# NBModule.net
KiCad netlist of a schematic drawn in Altium Designer
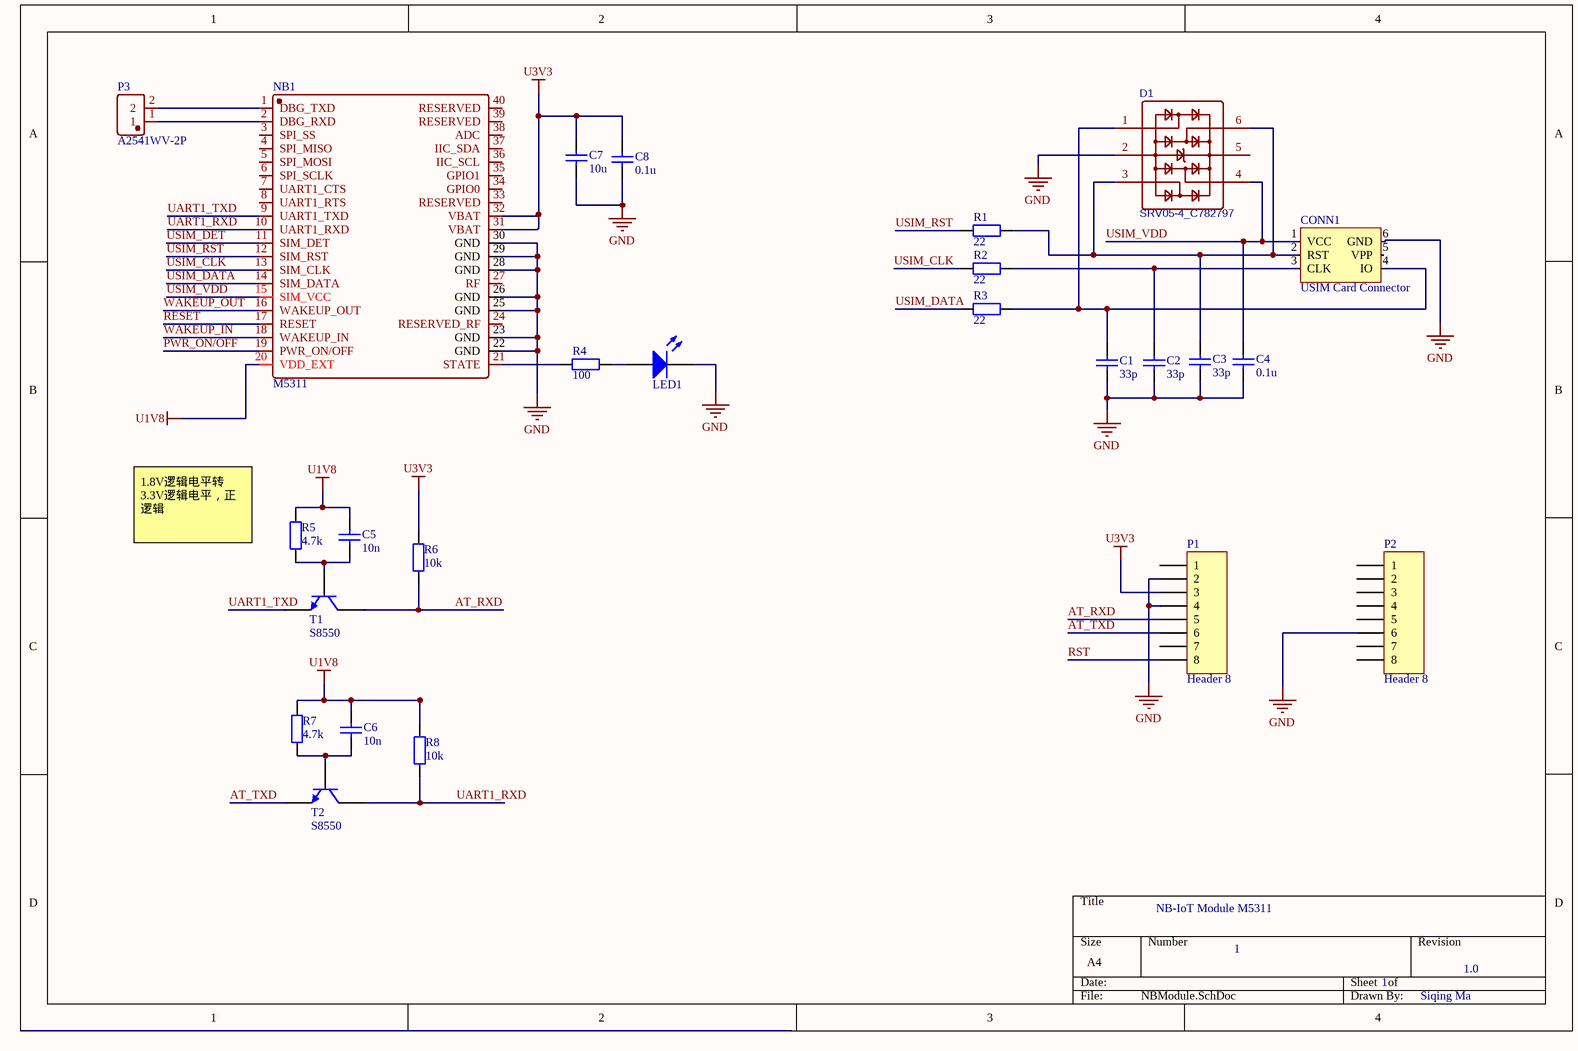
[diagram p0: NBModule.SchDoc]

(export (version "E")
  (design (tool "Eeschema 10.0.6"))
  (components
    (comp (ref "C1")
      (value "33p")
      (footprint "C 1206")
      (description "1206贴片电容")
      (libsource (lib "02-Miscellaneous_Devices_ZSF_Library") (part "Cap_1206"))
    )
    (comp (ref "C2")
      (value "33p")
      (footprint "C 1206")
      (description "1206贴片电容")
      (libsource (lib "02-Miscellaneous_Devices_ZSF_Library") (part "Cap_1206"))
    )
    (comp (ref "C3")
      (value "33p")
      (footprint "C 1206")
      (description "1206贴片电容")
      (libsource (lib "02-Miscellaneous_Devices_ZSF_Library") (part "Cap_1206"))
    )
    (comp (ref "C4")
      (value "0.1u")
      (footprint "C 1206")
      (description "1206贴片电容")
      (libsource (lib "02-Miscellaneous_Devices_ZSF_Library") (part "Cap_1206"))
    )
    (comp (ref "C5")
      (value "10n")
      (footprint "C 1206")
      (description "1206贴片电容")
      (libsource (lib "02-Miscellaneous_Devices_ZSF_Library") (part "Cap_1206"))
    )
    (comp (ref "C6")
      (value "10n")
      (footprint "C 1206")
      (description "1206贴片电容")
      (libsource (lib "02-Miscellaneous_Devices_ZSF_Library") (part "Cap_1206"))
    )
    (comp (ref "C7")
      (value "10u")
      (footprint "C 1206")
      (description "1206贴片电容")
      (libsource (lib "02-Miscellaneous_Devices_ZSF_Library") (part "Cap_1206"))
    )
    (comp (ref "C8")
      (value "0.1u")
      (footprint "C 1206")
      (description "1206贴片电容")
      (libsource (lib "02-Miscellaneous_Devices_ZSF_Library") (part "Cap_1206"))
    )
    (comp (ref "CONN1")
      (value "USIM Card Connector")
      (footprint "SIM-SMD_SMO-1512")
      (libsource (lib "NBIoT") (part "USIM Card Connector"))
    )
    (comp (ref "D1")
      (value "SRV05-4_C782797")
      (footprint "SOT-23-6_L2.9-W1.6-P0.95-LS2.8-BR")
      (fields
        (field (name "BOM_SUPPLIER PART") "C782797")
        (field (name "BOM_MANUFACTURER PART") "SRV05-4")
        (field (name "CONTRIBUTOR") "LCSC")
      )
      (libsource (lib "NBIoT") (part "SRV05-4_C782797"))
    )
    (comp (ref "LED1")
      (value "LED Chip")
      (footprint "LED 1206R")
      (description "Typical Chip LED")
      (fields (field (name "PUBLISHER") "Altium Limited"))
      (libsource (lib "03-EButterflyIntegratedLibrary") (part "LED Chip"))
    )
    (comp (ref "NB1") (value "M5311") (footprint "M5311") (libsource (lib "NBIoT") (part "M5311")))
    (comp (ref "P1")
      (value "Header 8")
      (footprint "HDR1X8")
      (description "Header, 8-Pin")
      (fields (field (name "PUBLISHER") "Altium Limited"))
      (libsource (lib "Miscellaneous Connectors") (part "Header 8"))
    )
    (comp (ref "P2")
      (value "Header 8")
      (footprint "HDR1X8")
      (description "Header, 8-Pin")
      (fields (field (name "PUBLISHER") "Altium Limited"))
      (libsource (lib "Miscellaneous Connectors") (part "Header 8"))
    )
    (comp (ref "P3")
      (value "A2541WV-2P")
      (footprint "HDR-TH_P2.54-H-M_A2541WV-2P")
      (libsource (lib "NBIoT") (part "A2541WV-2P"))
    )
    (comp (ref "R1")
      (value "22")
      (footprint "R 0805")
      (description "0805贴片电阻")
      (libsource (lib "02-Miscellaneous_Devices_ZSF_Library") (part "Res_0805"))
    )
    (comp (ref "R2")
      (value "22")
      (footprint "R 0805")
      (description "0805贴片电阻")
      (libsource (lib "02-Miscellaneous_Devices_ZSF_Library") (part "Res_0805"))
    )
    (comp (ref "R3")
      (value "22")
      (footprint "R 0805")
      (description "0805贴片电阻")
      (libsource (lib "02-Miscellaneous_Devices_ZSF_Library") (part "Res_0805"))
    )
    (comp (ref "R4")
      (value "100")
      (footprint "R 0805")
      (description "0805贴片电阻")
      (libsource (lib "02-Miscellaneous_Devices_ZSF_Library") (part "Res_0805"))
    )
    (comp (ref "R5")
      (value "4.7k")
      (footprint "R 0805")
      (description "0805贴片电阻")
      (libsource (lib "") (part "Res_0805_1"))
    )
    (comp (ref "R6")
      (value "10k")
      (footprint "R 0805")
      (description "0805贴片电阻")
      (libsource (lib "") (part "Res_0805_1"))
    )
    (comp (ref "R7")
      (value "4.7k")
      (footprint "R 0805")
      (description "0805贴片电阻")
      (libsource (lib "") (part "Res_0805_1"))
    )
    (comp (ref "R8")
      (value "10k")
      (footprint "R 0805")
      (description "0805贴片电阻")
      (libsource (lib "") (part "Res_0805_1"))
    )
    (comp (ref "T1")
      (value "S8550")
      (footprint "SOT-23B_N")
      (description "NPN Bipolar Transistor")
      (fields (field (name "PUBLISHER") "Altium Limited"))
      (libsource (lib "Miscellaneous Devices") (part "QNPN"))
    )
    (comp (ref "T2")
      (value "S8550")
      (footprint "SOT-23B_N")
      (description "NPN Bipolar Transistor")
      (fields (field (name "PUBLISHER") "Altium Limited"))
      (libsource (lib "Miscellaneous Devices") (part "QNPN"))
    )
  )
  (nets
    (net (code "1") (name "/AT_RXD") (class "Default")
      (node (ref "P1") (pin "5") (pinfunction "5_5") (pintype "passive"))
      (node (ref "R6") (pin "2") (pinfunction "2_2") (pintype "passive"))
      (node (ref "T1") (pin "1") (pinfunction "C_1") (pintype "passive"))
    )
    (net (code "2") (name "/AT_TXD") (class "Default")
      (node (ref "P1") (pin "6") (pinfunction "6_6") (pintype "passive"))
      (node (ref "T2") (pin "3") (pinfunction "E_3") (pintype "passive"))
    )
    (net (code "3") (name "/PWR_ON{slash}OFF") (class "Default")
      (node (ref "NB1") (pin "19") (pinfunction "PWR_ON/OFF_19") (pintype "passive"))
    )
    (net (code "4") (name "/RESET") (class "Default")
      (node (ref "NB1") (pin "17") (pinfunction "RESET_17") (pintype "passive"))
    )
    (net (code "5") (name "/RST") (class "Default")
      (node (ref "P1") (pin "8") (pinfunction "8_8") (pintype "passive"))
    )
    (net (code "6") (name "/UART1_RXD") (class "Default")
      (node (ref "NB1") (pin "10") (pinfunction "UART1_RXD_10") (pintype "passive"))
      (node (ref "R8") (pin "2") (pinfunction "2_2") (pintype "passive"))
      (node (ref "T2") (pin "1") (pinfunction "C_1") (pintype "passive"))
    )
    (net (code "7") (name "/UART1_TXD") (class "Default")
      (node (ref "NB1") (pin "9") (pinfunction "UART1_TXD_9") (pintype "passive"))
      (node (ref "T1") (pin "3") (pinfunction "E_3") (pintype "passive"))
    )
    (net (code "8") (name "/USIM_CLK") (class "Default")
      (node (ref "NB1") (pin "13") (pinfunction "SIM_CLK_13") (pintype "passive"))
      (node (ref "R2") (pin "2") (pinfunction "2_2") (pintype "passive"))
    )
    (net (code "9") (name "/USIM_DATA") (class "Default")
      (node (ref "NB1") (pin "14") (pinfunction "SIM_DATA_14") (pintype "passive"))
      (node (ref "R3") (pin "2") (pinfunction "2_2") (pintype "passive"))
    )
    (net (code "10") (name "/USIM_DET") (class "Default")
      (node (ref "NB1") (pin "11") (pinfunction "SIM_DET_11") (pintype "passive"))
    )
    (net (code "11") (name "/USIM_RST") (class "Default")
      (node (ref "NB1") (pin "12") (pinfunction "SIM_RST_12") (pintype "passive"))
      (node (ref "R1") (pin "2") (pinfunction "2_2") (pintype "passive"))
    )
    (net (code "12") (name "/USIM_VDD") (class "Default")
      (node (ref "C4") (pin "2") (pinfunction "2_2") (pintype "passive"))
      (node (ref "CONN1") (pin "1") (pinfunction "VCC_1") (pintype "bidirectional"))
      (node (ref "D1") (pin "4") (pinfunction "4_4") (pintype "passive"))
      (node (ref "NB1") (pin "15") (pinfunction "SIM_VCC_15") (pintype "passive"))
    )
    (net (code "13") (name "/WAKEUP_IN") (class "Default")
      (node (ref "NB1") (pin "18") (pinfunction "WAKEUP_IN_18") (pintype "passive"))
    )
    (net (code "14") (name "/WAKEUP_OUT") (class "Default")
      (node (ref "NB1") (pin "16") (pinfunction "WAKEUP_OUT_16") (pintype "passive"))
    )
    (net (code "15") (name "GND") (class "Default")
      (node (ref "C1") (pin "1") (pinfunction "1_1") (pintype "passive"))
      (node (ref "C2") (pin "1") (pinfunction "1_1") (pintype "passive"))
      (node (ref "C3") (pin "1") (pinfunction "1_1") (pintype "passive"))
      (node (ref "C4") (pin "1") (pinfunction "1_1") (pintype "passive"))
      (node (ref "C7") (pin "1") (pinfunction "1_1") (pintype "passive"))
      (node (ref "C8") (pin "1") (pinfunction "1_1") (pintype "passive"))
      (node (ref "CONN1") (pin "6") (pinfunction "GND_6") (pintype "bidirectional"))
      (node (ref "D1") (pin "2") (pinfunction "2_2") (pintype "passive"))
      (node (ref "LED1") (pin "2") (pinfunction "K_2") (pintype "passive"))
      (node (ref "NB1") (pin "22") (pinfunction "GND_22") (pintype "passive"))
      (node (ref "NB1") (pin "23") (pinfunction "GND_23") (pintype "passive"))
      (node (ref "NB1") (pin "25") (pinfunction "GND_25") (pintype "passive"))
      (node (ref "NB1") (pin "26") (pinfunction "GND_26") (pintype "passive"))
      (node (ref "NB1") (pin "28") (pinfunction "GND_28") (pintype "passive"))
      (node (ref "NB1") (pin "29") (pinfunction "GND_29") (pintype "passive"))
      (node (ref "NB1") (pin "30") (pinfunction "GND_30") (pintype "passive"))
      (node (ref "P1") (pin "2") (pinfunction "2_2") (pintype "passive"))
      (node (ref "P1") (pin "4") (pinfunction "4_4") (pintype "passive"))
      (node (ref "P2") (pin "6") (pinfunction "6_6") (pintype "passive"))
    )
    (net (code "16") (name "Net-(CONN1-CLK)") (class "Default")
      (node (ref "C2") (pin "2") (pinfunction "2_2") (pintype "passive"))
      (node (ref "CONN1") (pin "3") (pinfunction "CLK_3") (pintype "bidirectional"))
      (node (ref "R2") (pin "1") (pinfunction "1_1") (pintype "passive"))
    )
    (net (code "17") (name "Net-(CONN1-IO)") (class "Default")
      (node (ref "C1") (pin "2") (pinfunction "2_2") (pintype "passive"))
      (node (ref "CONN1") (pin "4") (pinfunction "IO_4") (pintype "bidirectional"))
      (node (ref "D1") (pin "1") (pinfunction "1_1") (pintype "passive"))
      (node (ref "R3") (pin "1") (pinfunction "1_1") (pintype "passive"))
    )
    (net (code "18") (name "Net-(CONN1-RST)") (class "Default")
      (node (ref "C3") (pin "2") (pinfunction "2_2") (pintype "passive"))
      (node (ref "CONN1") (pin "2") (pinfunction "RST_2") (pintype "bidirectional"))
      (node (ref "D1") (pin "3") (pinfunction "3_3") (pintype "passive"))
      (node (ref "D1") (pin "6") (pinfunction "6_6") (pintype "passive"))
      (node (ref "R1") (pin "1") (pinfunction "1_1") (pintype "passive"))
    )
    (net (code "19") (name "Net-(LED1-A)") (class "Default")
      (node (ref "LED1") (pin "1") (pinfunction "A_1") (pintype "passive"))
      (node (ref "R4") (pin "1") (pinfunction "1_1") (pintype "passive"))
    )
    (net (code "20") (name "Net-(NB1-DBG_RXD)") (class "Default")
      (node (ref "NB1") (pin "2") (pinfunction "DBG_RXD_2") (pintype "passive"))
      (node (ref "P3") (pin "1") (pinfunction "1_1") (pintype "passive"))
    )
    (net (code "21") (name "Net-(NB1-DBG_TXD)") (class "Default")
      (node (ref "NB1") (pin "1") (pinfunction "DBG_TXD_1") (pintype "passive"))
      (node (ref "P3") (pin "2") (pinfunction "2_2") (pintype "passive"))
    )
    (net (code "22") (name "Net-(NB1-STATE)") (class "Default")
      (node (ref "NB1") (pin "21") (pinfunction "STATE_21") (pintype "passive"))
      (node (ref "R4") (pin "2") (pinfunction "2_2") (pintype "passive"))
    )
    (net (code "23") (name "Net-(T1-B)") (class "Default")
      (node (ref "C5") (pin "2") (pinfunction "2_2") (pintype "passive"))
      (node (ref "R5") (pin "2") (pinfunction "2_2") (pintype "passive"))
      (node (ref "T1") (pin "2") (pinfunction "B_2") (pintype "passive"))
    )
    (net (code "24") (name "Net-(T2-B)") (class "Default")
      (node (ref "C6") (pin "2") (pinfunction "2_2") (pintype "passive"))
      (node (ref "R7") (pin "2") (pinfunction "2_2") (pintype "passive"))
      (node (ref "T2") (pin "2") (pinfunction "B_2") (pintype "passive"))
    )
    (net (code "25") (name "U1V8") (class "Default")
      (node (ref "C5") (pin "1") (pinfunction "1_1") (pintype "passive"))
      (node (ref "C6") (pin "1") (pinfunction "1_1") (pintype "passive"))
      (node (ref "NB1") (pin "20") (pinfunction "VDD_EXT_20") (pintype "passive"))
      (node (ref "R5") (pin "1") (pinfunction "1_1") (pintype "passive"))
      (node (ref "R7") (pin "1") (pinfunction "1_1") (pintype "passive"))
      (node (ref "R8") (pin "1") (pinfunction "1_1") (pintype "passive"))
    )
    (net (code "26") (name "U3V3") (class "Default")
      (node (ref "C7") (pin "2") (pinfunction "2_2") (pintype "passive"))
      (node (ref "C8") (pin "2") (pinfunction "2_2") (pintype "passive"))
      (node (ref "NB1") (pin "31") (pinfunction "VBAT_31") (pintype "passive"))
      (node (ref "NB1") (pin "32") (pinfunction "VBAT_32") (pintype "passive"))
      (node (ref "P1") (pin "3") (pinfunction "3_3") (pintype "passive"))
      (node (ref "R6") (pin "1") (pinfunction "1_1") (pintype "passive"))
    )
    (net (code "27") (name "unconnected-(CONN1-VPP-Pad5)") (class "Default")
      (node (ref "CONN1") (pin "5") (pinfunction "VPP_5") (pintype "bidirectional"))
    )
    (net (code "28") (name "unconnected-(D1-Pad5)") (class "Default")
      (node (ref "D1") (pin "5") (pinfunction "5_5") (pintype "passive"))
    )
    (net (code "29") (name "unconnected-(NB1-ADC-Pad38)") (class "Default")
      (node (ref "NB1") (pin "38") (pinfunction "ADC_38") (pintype "passive"))
    )
    (net (code "30") (name "unconnected-(NB1-GPIO0-Pad34)") (class "Default")
      (node (ref "NB1") (pin "34") (pinfunction "GPIO0_34") (pintype "passive"))
    )
    (net (code "31") (name "unconnected-(NB1-GPIO1-Pad35)") (class "Default")
      (node (ref "NB1") (pin "35") (pinfunction "GPIO1_35") (pintype "passive"))
    )
    (net (code "32") (name "unconnected-(NB1-IIC_SCL-Pad36)") (class "Default")
      (node (ref "NB1") (pin "36") (pinfunction "IIC_SCL_36") (pintype "passive"))
    )
    (net (code "33") (name "unconnected-(NB1-IIC_SDA-Pad37)") (class "Default")
      (node (ref "NB1") (pin "37") (pinfunction "IIC_SDA_37") (pintype "passive"))
    )
    (net (code "34") (name "unconnected-(NB1-RESERVED-Pad33)") (class "Default")
      (node (ref "NB1") (pin "33") (pinfunction "RESERVED_33") (pintype "passive"))
    )
    (net (code "35") (name "unconnected-(NB1-RESERVED-Pad39)") (class "Default")
      (node (ref "NB1") (pin "39") (pinfunction "RESERVED_39") (pintype "passive"))
    )
    (net (code "36") (name "unconnected-(NB1-RESERVED-Pad40)") (class "Default")
      (node (ref "NB1") (pin "40") (pinfunction "RESERVED_40") (pintype "passive"))
    )
    (net (code "37") (name "unconnected-(NB1-RESERVED_RF-Pad24)") (class "Default")
      (node (ref "NB1") (pin "24") (pinfunction "RESERVED_RF_24") (pintype "passive"))
    )
    (net (code "38") (name "unconnected-(NB1-RF-Pad27)") (class "Default")
      (node (ref "NB1") (pin "27") (pinfunction "RF_27") (pintype "passive"))
    )
    (net (code "39") (name "unconnected-(NB1-SPI_MISO-Pad4)") (class "Default")
      (node (ref "NB1") (pin "4") (pinfunction "SPI_MISO_4") (pintype "passive"))
    )
    (net (code "40") (name "unconnected-(NB1-SPI_MOSI-Pad5)") (class "Default")
      (node (ref "NB1") (pin "5") (pinfunction "SPI_MOSI_5") (pintype "passive"))
    )
    (net (code "41") (name "unconnected-(NB1-SPI_SCLK-Pad6)") (class "Default")
      (node (ref "NB1") (pin "6") (pinfunction "SPI_SCLK_6") (pintype "passive"))
    )
    (net (code "42") (name "unconnected-(NB1-SPI_SS-Pad3)") (class "Default")
      (node (ref "NB1") (pin "3") (pinfunction "SPI_SS_3") (pintype "passive"))
    )
    (net (code "43") (name "unconnected-(NB1-UART1_CTS-Pad7)") (class "Default")
      (node (ref "NB1") (pin "7") (pinfunction "UART1_CTS_7") (pintype "passive"))
    )
    (net (code "44") (name "unconnected-(NB1-UART1_RTS-Pad8)") (class "Default")
      (node (ref "NB1") (pin "8") (pinfunction "UART1_RTS_8") (pintype "passive"))
    )
    (net (code "45") (name "unconnected-(P1-Pad1)") (class "Default")
      (node (ref "P1") (pin "1") (pinfunction "1_1") (pintype "passive"))
    )
    (net (code "46") (name "unconnected-(P1-Pad7)") (class "Default")
      (node (ref "P1") (pin "7") (pinfunction "7_7") (pintype "passive"))
    )
    (net (code "47") (name "unconnected-(P2-Pad1)") (class "Default")
      (node (ref "P2") (pin "1") (pinfunction "1_1") (pintype "passive"))
    )
    (net (code "48") (name "unconnected-(P2-Pad2)") (class "Default")
      (node (ref "P2") (pin "2") (pinfunction "2_2") (pintype "passive"))
    )
    (net (code "49") (name "unconnected-(P2-Pad3)") (class "Default")
      (node (ref "P2") (pin "3") (pinfunction "3_3") (pintype "passive"))
    )
    (net (code "50") (name "unconnected-(P2-Pad4)") (class "Default")
      (node (ref "P2") (pin "4") (pinfunction "4_4") (pintype "passive"))
    )
    (net (code "51") (name "unconnected-(P2-Pad5)") (class "Default")
      (node (ref "P2") (pin "5") (pinfunction "5_5") (pintype "passive"))
    )
    (net (code "52") (name "unconnected-(P2-Pad7)") (class "Default")
      (node (ref "P2") (pin "7") (pinfunction "7_7") (pintype "passive"))
    )
    (net (code "53") (name "unconnected-(P2-Pad8)") (class "Default")
      (node (ref "P2") (pin "8") (pinfunction "8_8") (pintype "passive"))
    )
  )
)
